# SmartSwitch.net
KiCad netlist of a schematic drawn in EAGLE
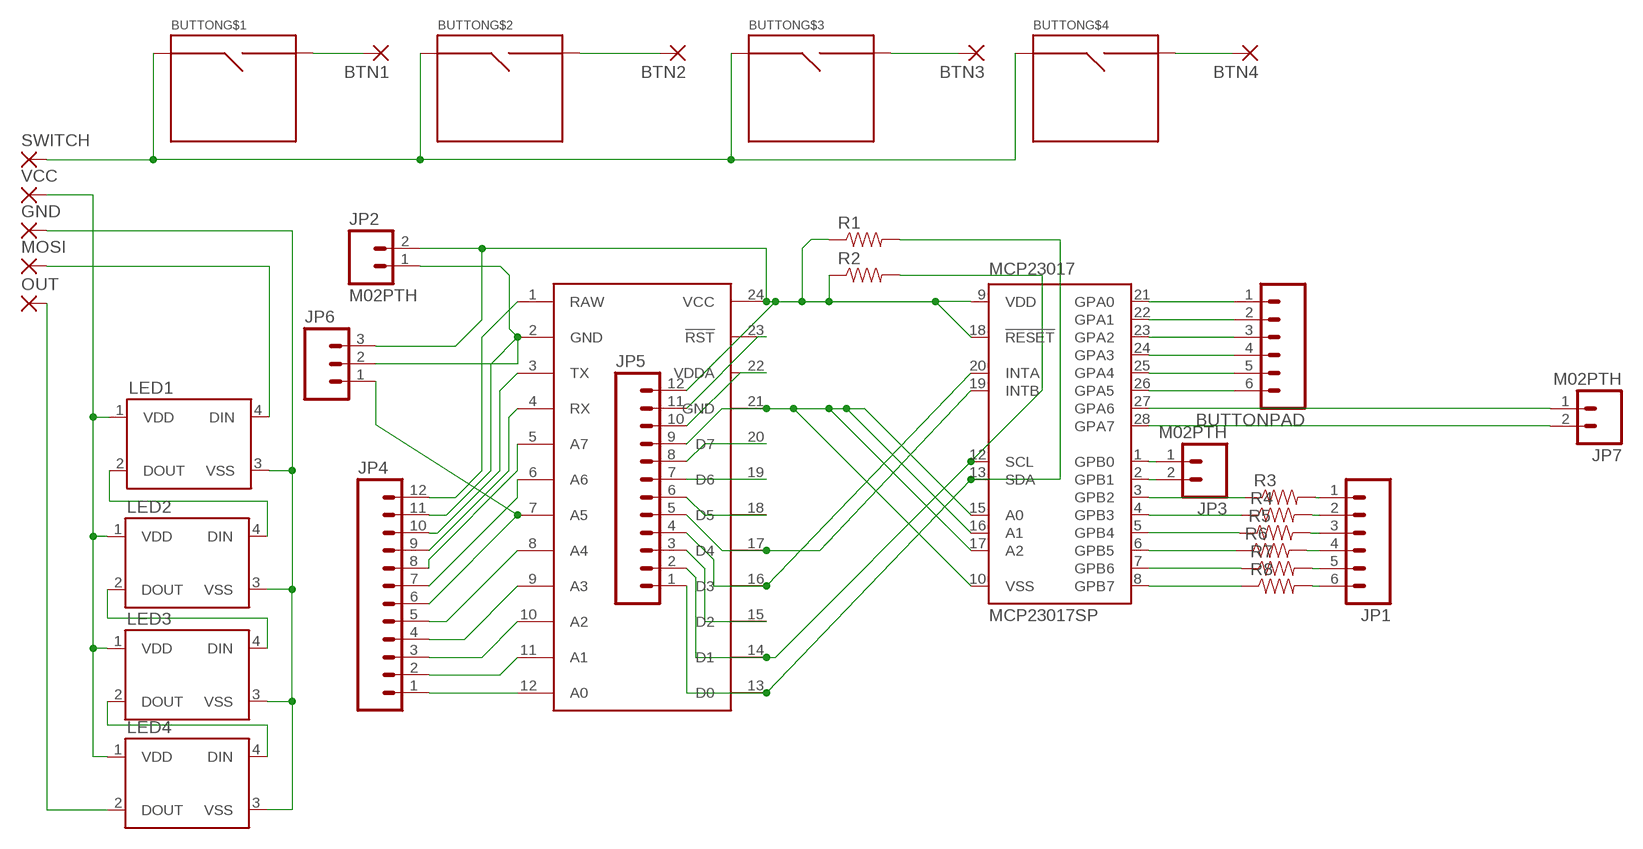
[diagram p0: schematic, sheet 1]

(export (version "E")
  (design (tool "Eeschema 10.0.6"))
  (components
    (comp (ref "BTN1")
      (value "2,15/1,0")
      (footprint "eagle-import:2,15_1,0")
      (libsource (lib "eagle-import") (part "2,15/1,0"))
    )
    (comp (ref "BTN2")
      (value "2,15/1,0")
      (footprint "eagle-import:2,15_1,0")
      (libsource (lib "eagle-import") (part "2,15/1,0"))
    )
    (comp (ref "BTN3")
      (value "2,15/1,0")
      (footprint "eagle-import:2,15_1,0")
      (libsource (lib "eagle-import") (part "2,15/1,0"))
    )
    (comp (ref "BTN4")
      (value "2,15/1,0")
      (footprint "eagle-import:2,15_1,0")
      (libsource (lib "eagle-import") (part "2,15/1,0"))
    )
    (comp (ref "BUTTON")
      (value "BUTTON")
      (footprint "eagle-import:BUTTON")
      (libsource (lib "eagle-import") (part "BUTTON"))
    )
    (comp (ref "BUTTONPAD")
      (value "M06SILK_FEMALE_PTH")
      (footprint "eagle-import:1X06")
      (libsource (lib "eagle-import") (part "M06SILK_FEMALE_PTH"))
    )
    (comp (ref "GND")
      (value "2,15/1,0")
      (footprint "eagle-import:2,15_1,0")
      (libsource (lib "eagle-import") (part "2,15/1,0"))
    )
    (comp (ref "JP1")
      (value "M06SILK_FEMALE_PTH")
      (footprint "eagle-import:1X06")
      (libsource (lib "eagle-import") (part "M06SILK_FEMALE_PTH"))
    )
    (comp (ref "JP2")
      (value "M02PTH")
      (footprint "eagle-import:1X02")
      (libsource (lib "eagle-import") (part "M02PTH"))
    )
    (comp (ref "JP3")
      (value "M02PTH")
      (footprint "eagle-import:1X02")
      (libsource (lib "eagle-import") (part "M02PTH"))
    )
    (comp (ref "JP4")
      (value "M12PTH")
      (footprint "eagle-import:1X12-SMALL-PADS")
      (libsource (lib "eagle-import") (part "M12PTH"))
    )
    (comp (ref "JP5")
      (value "M12PTH")
      (footprint "eagle-import:1X12-SMALL-PADS")
      (libsource (lib "eagle-import") (part "M12PTH"))
    )
    (comp (ref "JP6")
      (value "M03PTH")
      (footprint "eagle-import:1X03")
      (libsource (lib "eagle-import") (part "M03PTH"))
    )
    (comp (ref "JP7")
      (value "M02PTH")
      (footprint "eagle-import:1X02")
      (libsource (lib "eagle-import") (part "M02PTH"))
    )
    (comp (ref "LED1")
      (value "WS2812B")
      (footprint "eagle-import:WS2812B")
      (libsource (lib "eagle-import") (part "WS2812B"))
    )
    (comp (ref "LED2")
      (value "WS2812B")
      (footprint "eagle-import:WS2812B")
      (libsource (lib "eagle-import") (part "WS2812B"))
    )
    (comp (ref "LED3")
      (value "WS2812B")
      (footprint "eagle-import:WS2812B")
      (libsource (lib "eagle-import") (part "WS2812B"))
    )
    (comp (ref "LED4")
      (value "WS2812B")
      (footprint "eagle-import:WS2812B")
      (libsource (lib "eagle-import") (part "WS2812B"))
    )
    (comp (ref "MCP23017")
      (value "MCP23017SP")
      (footprint "eagle-import:DIL28-3")
      (libsource (lib "eagle-import") (part "MCP23017SP"))
    )
    (comp (ref "MOSI")
      (value "2,15/1,0")
      (footprint "eagle-import:2,15_1,0")
      (libsource (lib "eagle-import") (part "2,15/1,0"))
    )
    (comp (ref "OUT")
      (value "2,15/1,0")
      (footprint "eagle-import:2,15_1,0")
      (libsource (lib "eagle-import") (part "2,15/1,0"))
    )
    (comp (ref "R1")
      (value "RESISTORPTH-1/4W")
      (footprint "eagle-import:AXIAL-0.4")
      (libsource (lib "eagle-import") (part "RESISTORPTH-1/4W"))
    )
    (comp (ref "R2")
      (value "RESISTORPTH-1/4W")
      (footprint "eagle-import:AXIAL-0.4")
      (libsource (lib "eagle-import") (part "RESISTORPTH-1/4W"))
    )
    (comp (ref "R3")
      (value "RESISTORPTH-1/4W")
      (footprint "eagle-import:AXIAL-0.4")
      (libsource (lib "eagle-import") (part "RESISTORPTH-1/4W"))
    )
    (comp (ref "R4")
      (value "RESISTORPTH-1/4W")
      (footprint "eagle-import:AXIAL-0.4")
      (libsource (lib "eagle-import") (part "RESISTORPTH-1/4W"))
    )
    (comp (ref "R5")
      (value "RESISTORPTH-1/4W")
      (footprint "eagle-import:AXIAL-0.4")
      (libsource (lib "eagle-import") (part "RESISTORPTH-1/4W"))
    )
    (comp (ref "R6")
      (value "RESISTORPTH-1/4W")
      (footprint "eagle-import:AXIAL-0.4")
      (libsource (lib "eagle-import") (part "RESISTORPTH-1/4W"))
    )
    (comp (ref "R7")
      (value "RESISTORPTH-1/4W")
      (footprint "eagle-import:AXIAL-0.4")
      (libsource (lib "eagle-import") (part "RESISTORPTH-1/4W"))
    )
    (comp (ref "R8")
      (value "RESISTORPTH-1/4W")
      (footprint "eagle-import:AXIAL-0.4")
      (libsource (lib "eagle-import") (part "RESISTORPTH-1/4W"))
    )
    (comp (ref "SPARK")
      (value "SPARK_CORECORE")
      (footprint "eagle-import:SPARK_CORE")
      (libsource (lib "eagle-import") (part "SPARK_CORECORE"))
    )
    (comp (ref "SWITCH")
      (value "2,15/1,0")
      (footprint "eagle-import:2,15_1,0")
      (libsource (lib "eagle-import") (part "2,15/1,0"))
    )
    (comp (ref "VCC")
      (value "2,15/1,0")
      (footprint "eagle-import:2,15_1,0")
      (libsource (lib "eagle-import") (part "2,15/1,0"))
    )
  )
  (nets
    (net (code "1") (name "Net-(BTN1-P)") (class "Default")
      (node (ref "BTN1") (pin "1") (pinfunction "P_1") (pintype "passive"))
      (node (ref "BUTTON") (pin "SIG2") (pinfunction "SIG2_SIG2") (pintype "bidirectional"))
    )
    (net (code "2") (name "Net-(BTN2-P)") (class "Default")
      (node (ref "BTN2") (pin "1") (pinfunction "P_1") (pintype "passive"))
      (node (ref "BUTTON") (pin "SIG4") (pinfunction "SIG2_SIG4") (pintype "bidirectional"))
    )
    (net (code "3") (name "Net-(BTN3-P)") (class "Default")
      (node (ref "BTN3") (pin "1") (pinfunction "P_1") (pintype "passive"))
      (node (ref "BUTTON") (pin "SIG6") (pinfunction "SIG2_SIG6") (pintype "bidirectional"))
    )
    (net (code "4") (name "Net-(BTN4-P)") (class "Default")
      (node (ref "BTN4") (pin "1") (pinfunction "P_1") (pintype "passive"))
      (node (ref "BUTTON") (pin "SIG8") (pinfunction "SIG2_SIG8") (pintype "bidirectional"))
    )
    (net (code "5") (name "Net-(BUTTONB-SIG1)") (class "Default")
      (node (ref "BUTTON") (pin "SIG1") (pinfunction "SIG1_SIG1") (pintype "bidirectional"))
      (node (ref "BUTTON") (pin "SIG3") (pinfunction "SIG1_SIG3") (pintype "bidirectional"))
      (node (ref "BUTTON") (pin "SIG5") (pinfunction "SIG1_SIG5") (pintype "bidirectional"))
      (node (ref "BUTTON") (pin "SIG7") (pinfunction "SIG1_SIG7") (pintype "bidirectional"))
      (node (ref "SWITCH") (pin "1") (pinfunction "P_1") (pintype "passive"))
    )
    (net (code "6") (name "Net-(GND-P)") (class "Default")
      (node (ref "GND") (pin "1") (pinfunction "P_1") (pintype "passive"))
      (node (ref "LED1") (pin "3") (pinfunction "VSS_3") (pintype "power_in"))
      (node (ref "LED2") (pin "3") (pinfunction "VSS_3") (pintype "power_in"))
      (node (ref "LED3") (pin "3") (pinfunction "VSS_3") (pintype "power_in"))
      (node (ref "LED4") (pin "3") (pinfunction "VSS_3") (pintype "power_in"))
    )
    (net (code "7") (name "Net-(JP2-Pad1)") (class "Default")
      (node (ref "JP2") (pin "1") (pinfunction "1_1") (pintype "passive"))
      (node (ref "JP4") (pin "11") (pinfunction "11_11") (pintype "passive"))
      (node (ref "JP6") (pin "2") (pinfunction "2_2") (pintype "passive"))
      (node (ref "SPARK") (pin "2") (pinfunction "GND_2") (pintype "power_in"))
    )
    (net (code "8") (name "Net-(LED1-DIN)") (class "Default")
      (node (ref "LED1") (pin "4") (pinfunction "DIN_4") (pintype "input"))
      (node (ref "MOSI") (pin "1") (pinfunction "P_1") (pintype "passive"))
    )
    (net (code "9") (name "Net-(LED1-DOUT)") (class "Default")
      (node (ref "LED1") (pin "2") (pinfunction "DOUT_2") (pintype "output"))
      (node (ref "LED2") (pin "4") (pinfunction "DIN_4") (pintype "input"))
    )
    (net (code "10") (name "Net-(LED1-VDD)") (class "Default")
      (node (ref "LED1") (pin "1") (pinfunction "VDD_1") (pintype "power_in"))
      (node (ref "LED2") (pin "1") (pinfunction "VDD_1") (pintype "power_in"))
      (node (ref "LED3") (pin "1") (pinfunction "VDD_1") (pintype "power_in"))
      (node (ref "LED4") (pin "1") (pinfunction "VDD_1") (pintype "power_in"))
      (node (ref "VCC") (pin "1") (pinfunction "P_1") (pintype "passive"))
    )
    (net (code "11") (name "Net-(LED2-DOUT)") (class "Default")
      (node (ref "LED2") (pin "2") (pinfunction "DOUT_2") (pintype "output"))
      (node (ref "LED3") (pin "4") (pinfunction "DIN_4") (pintype "input"))
    )
    (net (code "12") (name "Net-(LED3-DOUT)") (class "Default")
      (node (ref "LED3") (pin "2") (pinfunction "DOUT_2") (pintype "output"))
      (node (ref "LED4") (pin "4") (pinfunction "DIN_4") (pintype "input"))
    )
    (net (code "13") (name "Net-(LED4-DOUT)") (class "Default")
      (node (ref "LED4") (pin "2") (pinfunction "DOUT_2") (pintype "output"))
      (node (ref "OUT") (pin "1") (pinfunction "P_1") (pintype "passive"))
    )
    (net (code "14") (name "Net-(MCP23017-A0)") (class "Default")
      (node (ref "JP5") (pin "9") (pinfunction "9_9") (pintype "passive"))
      (node (ref "MCP23017") (pin "10") (pinfunction "VSS_10") (pintype "power_in"))
      (node (ref "MCP23017") (pin "15") (pinfunction "A0_15") (pintype "input"))
      (node (ref "MCP23017") (pin "16") (pinfunction "A1_16") (pintype "input"))
      (node (ref "MCP23017") (pin "17") (pinfunction "A2_17") (pintype "input"))
      (node (ref "SPARK") (pin "21") (pinfunction "GND_21") (pintype "power_in"))
    )
    (net (code "15") (name "Net-(MCP23017-GPA0)") (class "Default")
      (node (ref "BUTTONPAD") (pin "1") (pinfunction "1_1") (pintype "passive"))
      (node (ref "MCP23017") (pin "21") (pinfunction "GPA0_21") (pintype "bidirectional"))
    )
    (net (code "16") (name "Net-(MCP23017-GPA1)") (class "Default")
      (node (ref "BUTTONPAD") (pin "2") (pinfunction "2_2") (pintype "passive"))
      (node (ref "MCP23017") (pin "22") (pinfunction "GPA1_22") (pintype "bidirectional"))
    )
    (net (code "17") (name "Net-(MCP23017-GPA2)") (class "Default")
      (node (ref "BUTTONPAD") (pin "3") (pinfunction "3_3") (pintype "passive"))
      (node (ref "MCP23017") (pin "23") (pinfunction "GPA2_23") (pintype "bidirectional"))
    )
    (net (code "18") (name "Net-(MCP23017-GPA3)") (class "Default")
      (node (ref "BUTTONPAD") (pin "4") (pinfunction "4_4") (pintype "passive"))
      (node (ref "MCP23017") (pin "24") (pinfunction "GPA3_24") (pintype "bidirectional"))
    )
    (net (code "19") (name "Net-(MCP23017-GPA4)") (class "Default")
      (node (ref "BUTTONPAD") (pin "5") (pinfunction "5_5") (pintype "passive"))
      (node (ref "MCP23017") (pin "25") (pinfunction "GPA4_25") (pintype "bidirectional"))
    )
    (net (code "20") (name "Net-(MCP23017-GPA5)") (class "Default")
      (node (ref "BUTTONPAD") (pin "6") (pinfunction "6_6") (pintype "passive"))
      (node (ref "MCP23017") (pin "26") (pinfunction "GPA5_26") (pintype "bidirectional"))
    )
    (net (code "21") (name "Net-(MCP23017-GPA6)") (class "Default")
      (node (ref "JP7") (pin "1") (pinfunction "1_1") (pintype "passive"))
      (node (ref "MCP23017") (pin "27") (pinfunction "GPA6_27") (pintype "bidirectional"))
    )
    (net (code "22") (name "Net-(MCP23017-GPA7)") (class "Default")
      (node (ref "JP7") (pin "2") (pinfunction "2_2") (pintype "passive"))
      (node (ref "MCP23017") (pin "28") (pinfunction "GPA7_28") (pintype "bidirectional"))
    )
    (net (code "23") (name "Net-(MCP23017-GPB0)") (class "Default")
      (node (ref "JP3") (pin "1") (pinfunction "1_1") (pintype "passive"))
      (node (ref "MCP23017") (pin "1") (pinfunction "GPB0_1") (pintype "bidirectional"))
    )
    (net (code "24") (name "Net-(MCP23017-GPB1)") (class "Default")
      (node (ref "JP3") (pin "2") (pinfunction "2_2") (pintype "passive"))
      (node (ref "MCP23017") (pin "2") (pinfunction "GPB1_2") (pintype "bidirectional"))
    )
    (net (code "25") (name "Net-(MCP23017-GPB2)") (class "Default")
      (node (ref "MCP23017") (pin "3") (pinfunction "GPB2_3") (pintype "bidirectional"))
      (node (ref "R3") (pin "P$1") (pinfunction "1_P$1") (pintype "passive"))
    )
    (net (code "26") (name "Net-(MCP23017-GPB3)") (class "Default")
      (node (ref "MCP23017") (pin "4") (pinfunction "GPB3_4") (pintype "bidirectional"))
      (node (ref "R4") (pin "P$1") (pinfunction "1_P$1") (pintype "passive"))
    )
    (net (code "27") (name "Net-(MCP23017-GPB4)") (class "Default")
      (node (ref "MCP23017") (pin "5") (pinfunction "GPB4_5") (pintype "bidirectional"))
      (node (ref "R5") (pin "P$1") (pinfunction "1_P$1") (pintype "passive"))
    )
    (net (code "28") (name "Net-(MCP23017-GPB5)") (class "Default")
      (node (ref "MCP23017") (pin "6") (pinfunction "GPB5_6") (pintype "bidirectional"))
      (node (ref "R6") (pin "P$1") (pinfunction "1_P$1") (pintype "passive"))
    )
    (net (code "29") (name "Net-(MCP23017-GPB6)") (class "Default")
      (node (ref "MCP23017") (pin "7") (pinfunction "GPB6_7") (pintype "bidirectional"))
      (node (ref "R7") (pin "P$1") (pinfunction "1_P$1") (pintype "passive"))
    )
    (net (code "30") (name "Net-(MCP23017-GPB7)") (class "Default")
      (node (ref "MCP23017") (pin "8") (pinfunction "GPB7_8") (pintype "bidirectional"))
      (node (ref "R8") (pin "P$1") (pinfunction "1_P$1") (pintype "passive"))
    )
    (net (code "31") (name "Net-(MCP23017-INTA)") (class "Default")
      (node (ref "JP5") (pin "4") (pinfunction "4_4") (pintype "passive"))
      (node (ref "MCP23017") (pin "20") (pinfunction "INTA_20") (pintype "output"))
      (node (ref "SPARK") (pin "16") (pinfunction "D3_16") (pintype "bidirectional"))
    )
    (net (code "32") (name "Net-(MCP23017-INTB)") (class "Default")
      (node (ref "JP5") (pin "5") (pinfunction "5_5") (pintype "passive"))
      (node (ref "MCP23017") (pin "19") (pinfunction "INTB_19") (pintype "output"))
      (node (ref "SPARK") (pin "17") (pinfunction "D4_17") (pintype "bidirectional"))
    )
    (net (code "33") (name "Net-(MCP23017-SCL)") (class "Default")
      (node (ref "JP5") (pin "2") (pinfunction "2_2") (pintype "passive"))
      (node (ref "MCP23017") (pin "12") (pinfunction "SCL_12") (pintype "input"))
      (node (ref "R2") (pin "P$2") (pinfunction "2_P$2") (pintype "passive"))
      (node (ref "SPARK") (pin "14") (pinfunction "D1_14") (pintype "bidirectional"))
    )
    (net (code "34") (name "Net-(MCP23017-SDA)") (class "Default")
      (node (ref "JP5") (pin "1") (pinfunction "1_1") (pintype "passive"))
      (node (ref "MCP23017") (pin "13") (pinfunction "SDA_13") (pintype "bidirectional"))
      (node (ref "R1") (pin "P$2") (pinfunction "2_P$2") (pintype "passive"))
      (node (ref "SPARK") (pin "13") (pinfunction "D0_13") (pintype "bidirectional"))
    )
    (net (code "35") (name "Net-(MCP23017-VDD)") (class "Default")
      (node (ref "JP2") (pin "2") (pinfunction "2_2") (pintype "passive"))
      (node (ref "JP5") (pin "12") (pinfunction "12_12") (pintype "passive"))
      (node (ref "JP6") (pin "3") (pinfunction "3_3") (pintype "passive"))
      (node (ref "MCP23017") (pin "18") (pinfunction "~{RESET}_18") (pintype "input"))
      (node (ref "MCP23017") (pin "9") (pinfunction "VDD_9") (pintype "power_in"))
      (node (ref "R1") (pin "P$1") (pinfunction "1_P$1") (pintype "passive"))
      (node (ref "R2") (pin "P$1") (pinfunction "1_P$1") (pintype "passive"))
      (node (ref "SPARK") (pin "24") (pinfunction "VCC_24") (pintype "power_in"))
    )
    (net (code "36") (name "Net-(R3-2)") (class "Default")
      (node (ref "JP1") (pin "1") (pinfunction "1_1") (pintype "passive"))
      (node (ref "R3") (pin "P$2") (pinfunction "2_P$2") (pintype "passive"))
    )
    (net (code "37") (name "Net-(R4-2)") (class "Default")
      (node (ref "JP1") (pin "2") (pinfunction "2_2") (pintype "passive"))
      (node (ref "R4") (pin "P$2") (pinfunction "2_P$2") (pintype "passive"))
    )
    (net (code "38") (name "Net-(R5-2)") (class "Default")
      (node (ref "JP1") (pin "3") (pinfunction "3_3") (pintype "passive"))
      (node (ref "R5") (pin "P$2") (pinfunction "2_P$2") (pintype "passive"))
    )
    (net (code "39") (name "Net-(R6-2)") (class "Default")
      (node (ref "JP1") (pin "4") (pinfunction "4_4") (pintype "passive"))
      (node (ref "R6") (pin "P$2") (pinfunction "2_P$2") (pintype "passive"))
    )
    (net (code "40") (name "Net-(R7-2)") (class "Default")
      (node (ref "JP1") (pin "5") (pinfunction "5_5") (pintype "passive"))
      (node (ref "R7") (pin "P$2") (pinfunction "2_P$2") (pintype "passive"))
    )
    (net (code "41") (name "Net-(R8-2)") (class "Default")
      (node (ref "JP1") (pin "6") (pinfunction "6_6") (pintype "passive"))
      (node (ref "R8") (pin "P$2") (pinfunction "2_P$2") (pintype "passive"))
    )
    (net (code "42") (name "Net-(SPARK-A0)") (class "Default")
      (node (ref "JP4") (pin "1") (pinfunction "1_1") (pintype "passive"))
      (node (ref "SPARK") (pin "12") (pinfunction "A0_12") (pintype "bidirectional"))
    )
    (net (code "43") (name "Net-(SPARK-A1)") (class "Default")
      (node (ref "JP4") (pin "2") (pinfunction "2_2") (pintype "passive"))
      (node (ref "SPARK") (pin "11") (pinfunction "A1_11") (pintype "bidirectional"))
    )
    (net (code "44") (name "Net-(SPARK-A2)") (class "Default")
      (node (ref "JP4") (pin "3") (pinfunction "3_3") (pintype "passive"))
      (node (ref "SPARK") (pin "10") (pinfunction "A2_10") (pintype "bidirectional"))
    )
    (net (code "45") (name "Net-(SPARK-A3)") (class "Default")
      (node (ref "JP4") (pin "4") (pinfunction "4_4") (pintype "passive"))
      (node (ref "SPARK") (pin "9") (pinfunction "A3_9") (pintype "bidirectional"))
    )
    (net (code "46") (name "Net-(SPARK-A4)") (class "Default")
      (node (ref "JP4") (pin "5") (pinfunction "5_5") (pintype "passive"))
      (node (ref "SPARK") (pin "8") (pinfunction "A4_8") (pintype "bidirectional"))
    )
    (net (code "47") (name "Net-(SPARK-A5)") (class "Default")
      (node (ref "JP4") (pin "6") (pinfunction "6_6") (pintype "passive"))
      (node (ref "JP6") (pin "1") (pinfunction "1_1") (pintype "passive"))
      (node (ref "SPARK") (pin "7") (pinfunction "A5_7") (pintype "bidirectional"))
    )
    (net (code "48") (name "Net-(SPARK-A6)") (class "Default")
      (node (ref "JP4") (pin "7") (pinfunction "7_7") (pintype "passive"))
      (node (ref "SPARK") (pin "6") (pinfunction "A6_6") (pintype "bidirectional"))
    )
    (net (code "49") (name "Net-(SPARK-A7)") (class "Default")
      (node (ref "JP4") (pin "8") (pinfunction "8_8") (pintype "passive"))
      (node (ref "SPARK") (pin "5") (pinfunction "A7_5") (pintype "bidirectional"))
    )
    (net (code "50") (name "Net-(SPARK-D2)") (class "Default")
      (node (ref "JP5") (pin "3") (pinfunction "3_3") (pintype "passive"))
      (node (ref "SPARK") (pin "15") (pinfunction "D2_15") (pintype "bidirectional"))
    )
    (net (code "51") (name "Net-(SPARK-D5)") (class "Default")
      (node (ref "JP5") (pin "6") (pinfunction "6_6") (pintype "passive"))
      (node (ref "SPARK") (pin "18") (pinfunction "D5_18") (pintype "bidirectional"))
    )
    (net (code "52") (name "Net-(SPARK-D6)") (class "Default")
      (node (ref "JP5") (pin "7") (pinfunction "7_7") (pintype "passive"))
      (node (ref "SPARK") (pin "19") (pinfunction "D6_19") (pintype "bidirectional"))
    )
    (net (code "53") (name "Net-(SPARK-D7)") (class "Default")
      (node (ref "JP5") (pin "8") (pinfunction "8_8") (pintype "passive"))
      (node (ref "SPARK") (pin "20") (pinfunction "D7_20") (pintype "bidirectional"))
    )
    (net (code "54") (name "Net-(SPARK-RAW)") (class "Default")
      (node (ref "JP4") (pin "12") (pinfunction "12_12") (pintype "passive"))
      (node (ref "SPARK") (pin "1") (pinfunction "RAW_1") (pintype "power_in"))
    )
    (net (code "55") (name "Net-(SPARK-RX)") (class "Default")
      (node (ref "JP4") (pin "9") (pinfunction "9_9") (pintype "passive"))
      (node (ref "SPARK") (pin "4") (pinfunction "RX_4") (pintype "bidirectional"))
    )
    (net (code "56") (name "Net-(SPARK-TX)") (class "Default")
      (node (ref "JP4") (pin "10") (pinfunction "10_10") (pintype "passive"))
      (node (ref "SPARK") (pin "3") (pinfunction "TX_3") (pintype "bidirectional"))
    )
    (net (code "57") (name "Net-(SPARK-VDDA)") (class "Default")
      (node (ref "JP5") (pin "10") (pinfunction "10_10") (pintype "passive"))
      (node (ref "SPARK") (pin "22") (pinfunction "VDDA_22") (pintype "power_in"))
    )
    (net (code "58") (name "Net-(SPARK-~{RST})") (class "Default")
      (node (ref "JP5") (pin "11") (pinfunction "11_11") (pintype "passive"))
      (node (ref "SPARK") (pin "23") (pinfunction "~{RST}_23") (pintype "bidirectional"))
    )
  )
)
